# CP2102-ESP01-adaptor.net
KiCad netlist of a schematic drawn in EAGLE
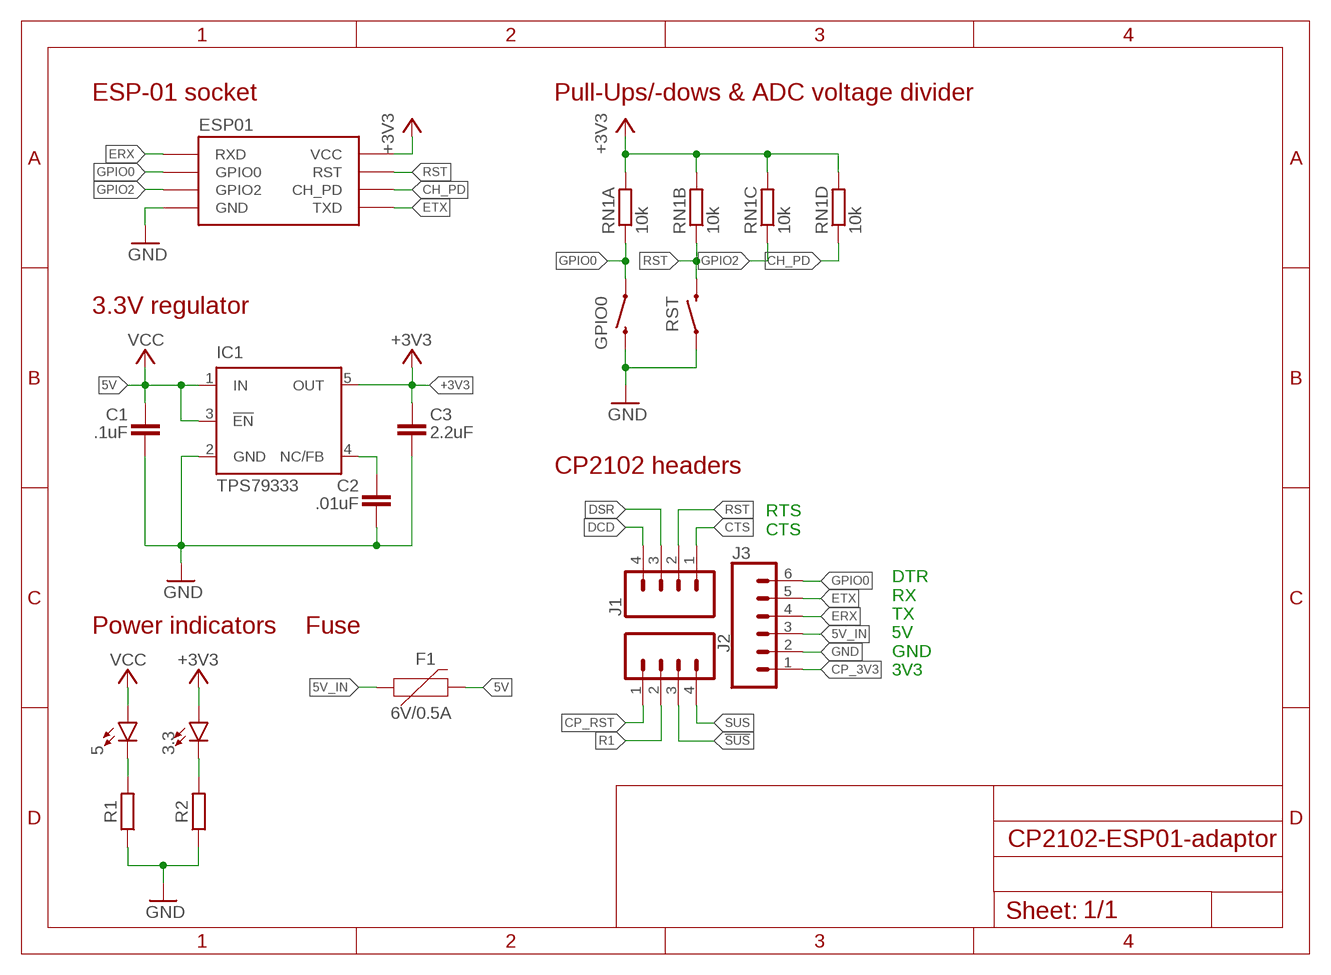
[diagram p0: schematic, sheet 1]

(export (version "E")
  (design (tool "Eeschema 10.0.6"))
  (components
    (comp (ref "3.3")
      (value "LED0603")
      (footprint "eagle-import:LED-0603")
      (libsource (lib "eagle-import") (part "LED0603"))
    )
    (comp (ref "5")
      (value "LED0603")
      (footprint "eagle-import:LED-0603")
      (libsource (lib "eagle-import") (part "LED0603"))
    )
    (comp (ref "C1")
      (value ".1uF")
      (footprint "eagle-import:C603")
      (libsource (lib "eagle-import") (part "CAPACITOR_NPOL-0603"))
    )
    (comp (ref "C2")
      (value ".01uF")
      (footprint "eagle-import:C603")
      (libsource (lib "eagle-import") (part "CAPACITOR_NPOL-0603"))
    )
    (comp (ref "C3")
      (value "2.2uF")
      (footprint "eagle-import:C603")
      (libsource (lib "eagle-import") (part "CAPACITOR_NPOL-0603"))
    )
    (comp (ref "ESP-01")
      (value "ESP01")
      (footprint "eagle-import:ESP01")
      (libsource (lib "eagle-import") (part "ESP01"))
    )
    (comp (ref "F1")
      (value "6V/0.5A")
      (footprint "eagle-import:1206")
      (libsource (lib "eagle-import") (part "PPTC_HALF-AMP"))
    )
    (comp (ref "GPIO0")
      (value "MOMENTARY-SWITCH-SPST-SMD-RIGHT-ANGLE")
      (footprint "eagle-import:TACTILE_SWITCH_SMD_RIGHT_ANGLE")
      (libsource (lib "eagle-import") (part "MOMENTARY-SWITCH-SPST-SMD-RIGHT-ANGLE"))
    )
    (comp (ref "IC1")
      (value "TPS79333")
      (footprint "eagle-import:SOT23-DBV")
      (fields (field (name "MF") "TEXAS INSTRUMENTS") (field (name "MPN") "TPS77033DBVT"))
      (libsource (lib "eagle-import") (part "TPS77033"))
    )
    (comp (ref "J1")
      (value "CONN_04LOCK")
      (footprint "eagle-import:1X04_LOCK")
      (libsource (lib "eagle-import") (part "CONN_04LOCK"))
    )
    (comp (ref "J2")
      (value "CONN_04LOCK")
      (footprint "eagle-import:1X04_LOCK")
      (libsource (lib "eagle-import") (part "CONN_04LOCK"))
    )
    (comp (ref "J3")
      (value "CONN_06LOCK")
      (footprint "eagle-import:1X06_LOCK")
      (libsource (lib "eagle-import") (part "CONN_06LOCK"))
    )
    (comp (ref "R1")
      (value "1k")
      (footprint "eagle-import:R603")
      (libsource (lib "eagle-import") (part "RESISTOR-0603"))
    )
    (comp (ref "R2")
      (value "1k")
      (footprint "eagle-import:R603")
      (libsource (lib "eagle-import") (part "RESISTOR-0603"))
    )
    (comp (ref "RN1")
      (value "10k")
      (footprint "eagle-import:RN8P-4R-CRA06S")
      (libsource (lib "eagle-import") (part "RESISTOR_ARRAY_4"))
    )
    (comp (ref "RST")
      (value "MOMENTARY-SWITCH-SPST-SMD-RIGHT-ANGLE")
      (footprint "eagle-import:TACTILE_SWITCH_SMD_RIGHT_ANGLE")
      (libsource (lib "eagle-import") (part "MOMENTARY-SWITCH-SPST-SMD-RIGHT-ANGLE"))
    )
  )
  (nets
    (net (code "1") (name "+3V3") (class "Default")
      (node (ref "3.3") (pin "A") (pinfunction "A_A") (pintype "passive"))
      (node (ref "C3") (pin "1") (pinfunction "1_1") (pintype "passive"))
      (node (ref "ESP-01") (pin "VCC") (pinfunction "VCC_VCC") (pintype "bidirectional"))
      (node (ref "IC1") (pin "5") (pinfunction "OUT_5") (pintype "passive"))
      (node (ref "RN1") (pin "5") (pinfunction "2_5") (pintype "passive"))
      (node (ref "RN1") (pin "6") (pinfunction "2_6") (pintype "passive"))
      (node (ref "RN1") (pin "7") (pinfunction "2_7") (pintype "passive"))
      (node (ref "RN1") (pin "8") (pinfunction "2_8") (pintype "passive"))
    )
    (net (code "2") (name "/~{SUS}") (class "Default")
      (node (ref "J2") (pin "3") (pinfunction "3_3") (pintype "passive"))
    )
    (net (code "3") (name "5V") (class "Default")
      (node (ref "5") (pin "A") (pinfunction "A_A") (pintype "passive"))
      (node (ref "C1") (pin "1") (pinfunction "1_1") (pintype "passive"))
      (node (ref "F1") (pin "2") (pinfunction "2_2") (pintype "bidirectional"))
      (node (ref "IC1") (pin "1") (pinfunction "IN_1") (pintype "input"))
      (node (ref "IC1") (pin "3") (pinfunction "~{EN}_3") (pintype "input"))
    )
    (net (code "4") (name "5V_IN") (class "Default")
      (node (ref "F1") (pin "1") (pinfunction "1_1") (pintype "bidirectional"))
      (node (ref "J3") (pin "3") (pinfunction "3_3") (pintype "passive"))
    )
    (net (code "5") (name "CH_PD") (class "Default")
      (node (ref "ESP-01") (pin "CH_PD") (pinfunction "CH_PD_CH_PD") (pintype "bidirectional"))
      (node (ref "RN1") (pin "4") (pinfunction "1_4") (pintype "passive"))
    )
    (net (code "6") (name "CP_3V3") (class "Default")
      (node (ref "J3") (pin "1") (pinfunction "1_1") (pintype "passive"))
    )
    (net (code "7") (name "CP_RST") (class "Default")
      (node (ref "J2") (pin "1") (pinfunction "1_1") (pintype "passive"))
    )
    (net (code "8") (name "CTS") (class "Default")
      (node (ref "J1") (pin "1") (pinfunction "1_1") (pintype "passive"))
    )
    (net (code "9") (name "DCD") (class "Default")
      (node (ref "J1") (pin "4") (pinfunction "4_4") (pintype "passive"))
    )
    (net (code "10") (name "DSR") (class "Default")
      (node (ref "J1") (pin "3") (pinfunction "3_3") (pintype "passive"))
    )
    (net (code "11") (name "ERX") (class "Default")
      (node (ref "ESP-01") (pin "RX") (pinfunction "RXD_RX") (pintype "bidirectional"))
      (node (ref "J3") (pin "4") (pinfunction "4_4") (pintype "passive"))
    )
    (net (code "12") (name "ETX") (class "Default")
      (node (ref "ESP-01") (pin "TX") (pinfunction "TXD_TX") (pintype "bidirectional"))
      (node (ref "J3") (pin "5") (pinfunction "5_5") (pintype "passive"))
    )
    (net (code "13") (name "GND") (class "Default")
      (node (ref "C1") (pin "2") (pinfunction "2_2") (pintype "passive"))
      (node (ref "C2") (pin "2") (pinfunction "2_2") (pintype "passive"))
      (node (ref "C3") (pin "2") (pinfunction "2_2") (pintype "passive"))
      (node (ref "ESP-01") (pin "GND") (pinfunction "GND_GND") (pintype "bidirectional"))
      (node (ref "GPIO0") (pin "2") (pinfunction "2_2") (pintype "passive"))
      (node (ref "IC1") (pin "2") (pinfunction "GND_2") (pintype "power_in"))
      (node (ref "J3") (pin "2") (pinfunction "2_2") (pintype "passive"))
      (node (ref "R1") (pin "1") (pinfunction "1_1") (pintype "passive"))
      (node (ref "R2") (pin "1") (pinfunction "1_1") (pintype "passive"))
      (node (ref "RST") (pin "1") (pinfunction "1_1") (pintype "passive"))
    )
    (net (code "14") (name "GPIO0") (class "Default")
      (node (ref "ESP-01") (pin "GPIO0") (pinfunction "GPIO0_GPIO0") (pintype "bidirectional"))
      (node (ref "GPIO0") (pin "1") (pinfunction "1_1") (pintype "passive"))
      (node (ref "J3") (pin "6") (pinfunction "6_6") (pintype "passive"))
      (node (ref "RN1") (pin "1") (pinfunction "1_1") (pintype "passive"))
    )
    (net (code "15") (name "GPIO2") (class "Default")
      (node (ref "ESP-01") (pin "GPIO2") (pinfunction "GPIO2_GPIO2") (pintype "bidirectional"))
      (node (ref "RN1") (pin "3") (pinfunction "1_3") (pintype "passive"))
    )
    (net (code "16") (name "Net-(3.3-PadC)") (class "Default")
      (node (ref "3.3") (pin "C") (pinfunction "C_C") (pintype "passive"))
      (node (ref "R2") (pin "2") (pinfunction "2_2") (pintype "passive"))
    )
    (net (code "17") (name "Net-(5-PadC)") (class "Default")
      (node (ref "5") (pin "C") (pinfunction "C_C") (pintype "passive"))
      (node (ref "R1") (pin "2") (pinfunction "2_2") (pintype "passive"))
    )
    (net (code "18") (name "Net-(IC1-NC{slash}FB)") (class "Default")
      (node (ref "C2") (pin "1") (pinfunction "1_1") (pintype "passive"))
      (node (ref "IC1") (pin "4") (pinfunction "NC/FB_4") (pintype "passive"))
    )
    (net (code "19") (name "R1") (class "Default")
      (node (ref "J2") (pin "2") (pinfunction "2_2") (pintype "passive"))
    )
    (net (code "20") (name "RST") (class "Default")
      (node (ref "ESP-01") (pin "RST") (pinfunction "RST_RST") (pintype "bidirectional"))
      (node (ref "J1") (pin "2") (pinfunction "2_2") (pintype "passive"))
      (node (ref "RN1") (pin "2") (pinfunction "1_2") (pintype "passive"))
      (node (ref "RST") (pin "2") (pinfunction "2_2") (pintype "passive"))
    )
    (net (code "21") (name "SUS") (class "Default")
      (node (ref "J2") (pin "4") (pinfunction "4_4") (pintype "passive"))
    )
  )
)
